# BatteryChecker.net
KiCad netlist of a schematic drawn in EAGLE
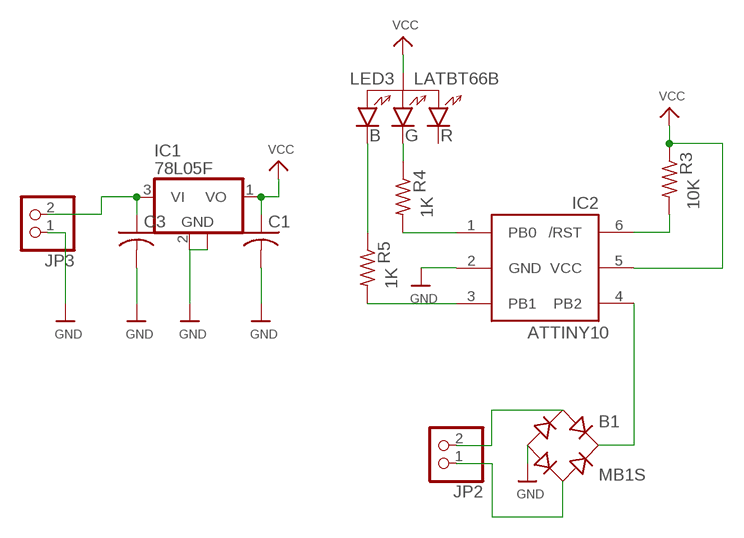
[diagram p0: schematic, sheet 1]

(export (version "E")
  (design (tool "Eeschema 10.0.6"))
  (components
    (comp (ref "B1")
      (value "MB1S")
      (footprint "eagle-import:SOIC-4")
      (libsource (lib "eagle-import") (part "MBS1"))
    )
    (comp (ref "C1")
      (value "C-USC0603")
      (footprint "eagle-import:C0603")
      (libsource (lib "eagle-import") (part "C-USC0603"))
    )
    (comp (ref "C3")
      (value "C-USC0603")
      (footprint "eagle-import:C0603")
      (libsource (lib "eagle-import") (part "C-USC0603"))
    )
    (comp (ref "IC1")
      (value "78L05F")
      (footprint "eagle-import:SOT89")
      (libsource (lib "eagle-import") (part "78LF05"))
    )
    (comp (ref "IC2")
      (value "ATTINY10")
      (footprint "eagle-import:SOT23-6")
      (libsource (lib "eagle-import") (part "ATTINY10"))
    )
    (comp (ref "JP2")
      (value "HEADER-1X2")
      (footprint "eagle-import:1X02_OVAL")
      (libsource (lib "eagle-import") (part "HEADER-1X2"))
    )
    (comp (ref "JP3")
      (value "HEADER-1X2")
      (footprint "eagle-import:1X02_OVAL")
      (libsource (lib "eagle-import") (part "HEADER-1X2"))
    )
    (comp (ref "LED3")
      (value "LATBT66B")
      (footprint "eagle-import:P-LCC-4")
      (libsource (lib "eagle-import") (part "LATBT66B"))
    )
    (comp (ref "R3")
      (value "R-US_R0603")
      (footprint "eagle-import:R0603")
      (fields (field (name "VAL") "10K"))
      (libsource (lib "eagle-import") (part "R-US_R0603"))
    )
    (comp (ref "R4")
      (value "R-US_R0603")
      (footprint "eagle-import:R0603")
      (fields (field (name "VAL") "1K"))
      (libsource (lib "eagle-import") (part "R-US_R0603"))
    )
    (comp (ref "R5")
      (value "R-US_R0603")
      (footprint "eagle-import:R0603")
      (fields (field (name "VAL") "1K"))
      (libsource (lib "eagle-import") (part "R-US_R0603"))
    )
  )
  (nets
    (net (code "1") (name "GND") (class "Default")
      (node (ref "B1") (pin "-") (pinfunction "-_-") (pintype "passive"))
      (node (ref "C1") (pin "2") (pinfunction "2_2") (pintype "passive"))
      (node (ref "C3") (pin "2") (pinfunction "2_2") (pintype "passive"))
      (node (ref "IC1") (pin "2") (pinfunction "GND_2") (pintype "passive"))
      (node (ref "IC1") (pin "2@1") (pinfunction "GND_2@1") (pintype "passive"))
      (node (ref "IC2") (pin "2") (pinfunction "GND_2") (pintype "power_in"))
      (node (ref "JP3") (pin "1") (pinfunction "1_1") (pintype "passive"))
    )
    (net (code "2") (name "Net-(B1-AC1)") (class "Default")
      (node (ref "B1") (pin "~1") (pinfunction "AC1_~1") (pintype "passive"))
      (node (ref "JP2") (pin "2") (pinfunction "2_2") (pintype "passive"))
    )
    (net (code "3") (name "Net-(B1-AC2)") (class "Default")
      (node (ref "B1") (pin "~2") (pinfunction "AC2_~2") (pintype "passive"))
      (node (ref "JP2") (pin "1") (pinfunction "1_1") (pintype "passive"))
    )
    (net (code "4") (name "Net-(IC1-VI)") (class "Default")
      (node (ref "C3") (pin "1") (pinfunction "1_1") (pintype "passive"))
      (node (ref "IC1") (pin "3") (pinfunction "VI_3") (pintype "input"))
      (node (ref "JP3") (pin "2") (pinfunction "2_2") (pintype "passive"))
    )
    (net (code "5") (name "Net-(IC2-PB0)") (class "Default")
      (node (ref "IC2") (pin "1") (pinfunction "PB0_1") (pintype "bidirectional"))
      (node (ref "R4") (pin "2") (pinfunction "2_2") (pintype "passive"))
    )
    (net (code "6") (name "Net-(IC2-PB1)") (class "Default")
      (node (ref "IC2") (pin "3") (pinfunction "PB1_3") (pintype "bidirectional"))
      (node (ref "R5") (pin "2") (pinfunction "2_2") (pintype "passive"))
    )
    (net (code "7") (name "Net-(IC2-PB2)") (class "Default")
      (node (ref "B1") (pin "+") (pinfunction "+_+") (pintype "passive"))
      (node (ref "IC2") (pin "4") (pinfunction "PB2_4") (pintype "bidirectional"))
    )
    (net (code "8") (name "Net-(IC2-{slash}RST)") (class "Default")
      (node (ref "IC2") (pin "6") (pinfunction "/RST_6") (pintype "bidirectional"))
      (node (ref "R3") (pin "2") (pinfunction "2_2") (pintype "passive"))
    )
    (net (code "9") (name "Net-(LED3-P$2)") (class "Default")
      (node (ref "LED3") (pin "P$3") (pinfunction "P$2_P$3") (pintype "bidirectional"))
      (node (ref "R5") (pin "1") (pinfunction "1_1") (pintype "passive"))
    )
    (net (code "10") (name "Net-(LED3-P$3)") (class "Default")
      (node (ref "LED3") (pin "P$4") (pinfunction "P$3_P$4") (pintype "bidirectional"))
      (node (ref "R4") (pin "1") (pinfunction "1_1") (pintype "passive"))
    )
    (net (code "11") (name "VCC") (class "Default")
      (node (ref "C1") (pin "1") (pinfunction "1_1") (pintype "passive"))
      (node (ref "IC1") (pin "1") (pinfunction "VO_1") (pintype "passive"))
      (node (ref "IC2") (pin "5") (pinfunction "VCC_5") (pintype "power_in"))
      (node (ref "LED3") (pin "P$2") (pinfunction "P$1_P$2") (pintype "bidirectional"))
      (node (ref "R3") (pin "1") (pinfunction "1_1") (pintype "passive"))
    )
    (net (code "12") (name "unconnected-(LED3-P$4-PadP$1)") (class "Default")
      (node (ref "LED3") (pin "P$1") (pinfunction "P$4_P$1") (pintype "bidirectional"))
    )
  )
)
